# kivez_rl_s.net
KiCad netlist of a schematic drawn in EAGLE
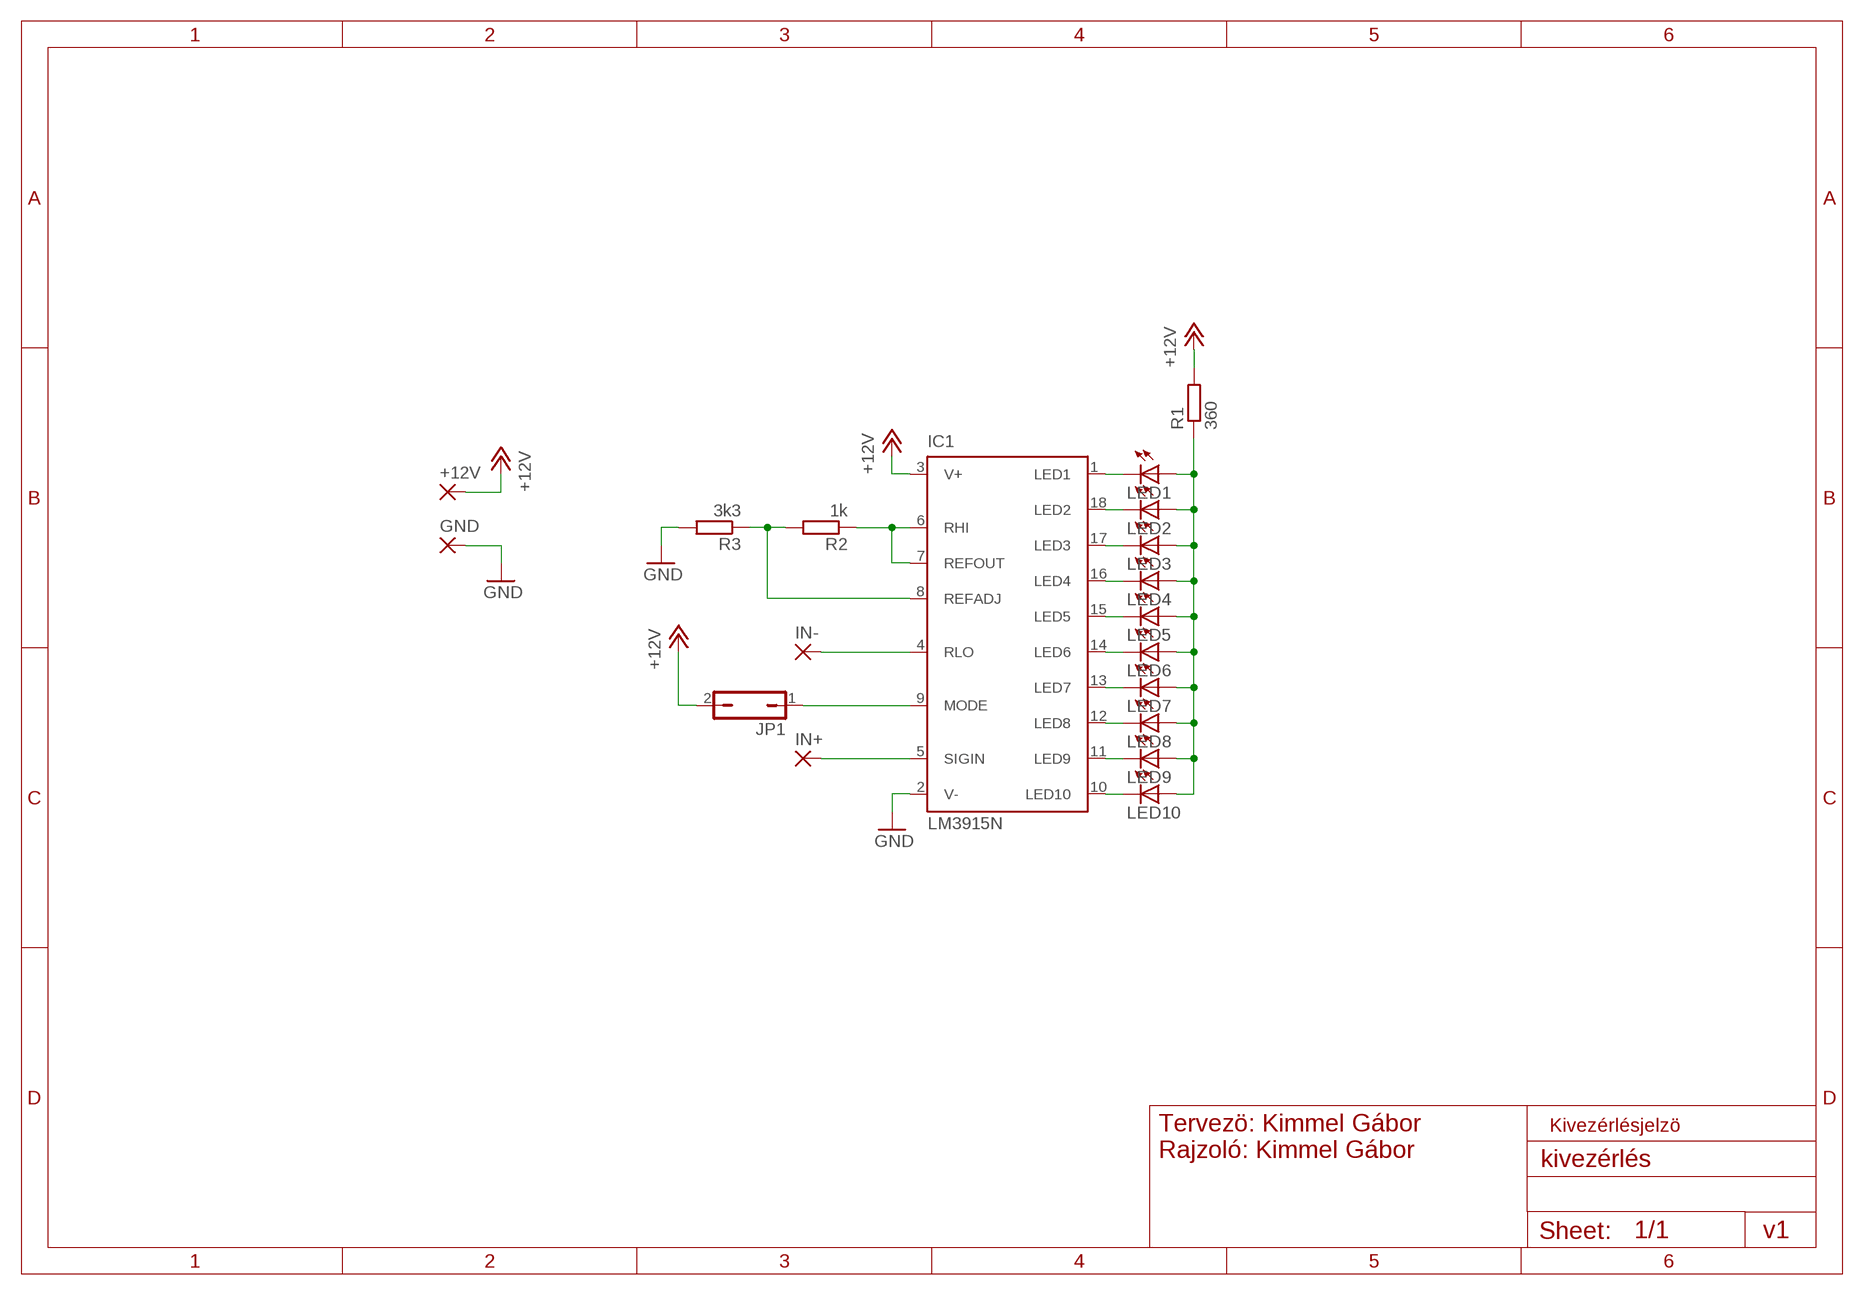
[diagram p0: schematic, sheet 1]

(export (version "E")
  (design (tool "Eeschema 10.0.6"))
  (components
    (comp (ref "+12V")
      (value "2,15/1,0")
      (footprint "eagle-import:2,15_1,0")
      (libsource (lib "eagle-import") (part "2,15/1,0"))
    )
    (comp (ref "GND")
      (value "2,15/1,0")
      (footprint "eagle-import:2,15_1,0")
      (libsource (lib "eagle-import") (part "2,15/1,0"))
    )
    (comp (ref "IC1")
      (value "LM3915N")
      (footprint "eagle-import:DIL18")
      (libsource (lib "eagle-import") (part "LM391N5"))
    )
    (comp (ref "IN+")
      (value "2,15/1,0")
      (footprint "eagle-import:2,15_1,0")
      (libsource (lib "eagle-import") (part "2,15/1,0"))
    )
    (comp (ref "IN-")
      (value "2,15/1,0")
      (footprint "eagle-import:2,15_1,0")
      (libsource (lib "eagle-import") (part "2,15/1,0"))
    )
    (comp (ref "JP1")
      (value "JP1Q")
      (footprint "eagle-import:JP1")
      (libsource (lib "eagle-import") (part "JP1Q"))
    )
    (comp (ref "LED1")
      (value "LED5MM")
      (footprint "eagle-import:LED5MM")
      (libsource (lib "eagle-import") (part "LED5MM"))
    )
    (comp (ref "LED2")
      (value "LED5MM")
      (footprint "eagle-import:LED5MM")
      (libsource (lib "eagle-import") (part "LED5MM"))
    )
    (comp (ref "LED3")
      (value "LED5MM")
      (footprint "eagle-import:LED5MM")
      (libsource (lib "eagle-import") (part "LED5MM"))
    )
    (comp (ref "LED4")
      (value "LED5MM")
      (footprint "eagle-import:LED5MM")
      (libsource (lib "eagle-import") (part "LED5MM"))
    )
    (comp (ref "LED5")
      (value "LED5MM")
      (footprint "eagle-import:LED5MM")
      (libsource (lib "eagle-import") (part "LED5MM"))
    )
    (comp (ref "LED6")
      (value "LED5MM")
      (footprint "eagle-import:LED5MM")
      (libsource (lib "eagle-import") (part "LED5MM"))
    )
    (comp (ref "LED7")
      (value "LED5MM")
      (footprint "eagle-import:LED5MM")
      (libsource (lib "eagle-import") (part "LED5MM"))
    )
    (comp (ref "LED8")
      (value "LED5MM")
      (footprint "eagle-import:LED5MM")
      (libsource (lib "eagle-import") (part "LED5MM"))
    )
    (comp (ref "LED9")
      (value "LED5MM")
      (footprint "eagle-import:LED5MM")
      (libsource (lib "eagle-import") (part "LED5MM"))
    )
    (comp (ref "LED10")
      (value "LED5MM")
      (footprint "eagle-import:LED5MM")
      (libsource (lib "eagle-import") (part "LED5MM"))
    )
    (comp (ref "R1")
      (value "360")
      (footprint "eagle-import:0309_12")
      (libsource (lib "eagle-import") (part "R-EU_0309/12"))
    )
    (comp (ref "R2")
      (value "1k")
      (footprint "eagle-import:0309_12")
      (libsource (lib "eagle-import") (part "R-EU_0309/12"))
    )
    (comp (ref "R3")
      (value "3k3")
      (footprint "eagle-import:0309_12")
      (libsource (lib "eagle-import") (part "R-EU_0309/12"))
    )
  )
  (nets
    (net (code "1") (name "+12V") (class "Default")
      (node (ref "+12V") (pin "1") (pinfunction "P_1") (pintype "passive"))
      (node (ref "IC1") (pin "3") (pinfunction "V+_3") (pintype "power_in"))
      (node (ref "JP1") (pin "2") (pinfunction "2_2") (pintype "passive"))
      (node (ref "R1") (pin "2") (pinfunction "2_2") (pintype "passive"))
    )
    (net (code "2") (name "GND") (class "Default")
      (node (ref "GND") (pin "1") (pinfunction "P_1") (pintype "passive"))
      (node (ref "IC1") (pin "2") (pinfunction "V-_2") (pintype "power_in"))
      (node (ref "R3") (pin "2") (pinfunction "2_2") (pintype "passive"))
    )
    (net (code "3") (name "Net-(IC1-LED1)") (class "Default")
      (node (ref "IC1") (pin "1") (pinfunction "LED1_1") (pintype "output"))
      (node (ref "LED1") (pin "K") (pinfunction "C_K") (pintype "passive"))
    )
    (net (code "4") (name "Net-(IC1-LED2)") (class "Default")
      (node (ref "IC1") (pin "18") (pinfunction "LED2_18") (pintype "output"))
      (node (ref "LED2") (pin "K") (pinfunction "C_K") (pintype "passive"))
    )
    (net (code "5") (name "Net-(IC1-LED3)") (class "Default")
      (node (ref "IC1") (pin "17") (pinfunction "LED3_17") (pintype "output"))
      (node (ref "LED3") (pin "K") (pinfunction "C_K") (pintype "passive"))
    )
    (net (code "6") (name "Net-(IC1-LED4)") (class "Default")
      (node (ref "IC1") (pin "16") (pinfunction "LED4_16") (pintype "output"))
      (node (ref "LED4") (pin "K") (pinfunction "C_K") (pintype "passive"))
    )
    (net (code "7") (name "Net-(IC1-LED5)") (class "Default")
      (node (ref "IC1") (pin "15") (pinfunction "LED5_15") (pintype "output"))
      (node (ref "LED5") (pin "K") (pinfunction "C_K") (pintype "passive"))
    )
    (net (code "8") (name "Net-(IC1-LED6)") (class "Default")
      (node (ref "IC1") (pin "14") (pinfunction "LED6_14") (pintype "output"))
      (node (ref "LED6") (pin "K") (pinfunction "C_K") (pintype "passive"))
    )
    (net (code "9") (name "Net-(IC1-LED7)") (class "Default")
      (node (ref "IC1") (pin "13") (pinfunction "LED7_13") (pintype "output"))
      (node (ref "LED7") (pin "K") (pinfunction "C_K") (pintype "passive"))
    )
    (net (code "10") (name "Net-(IC1-LED8)") (class "Default")
      (node (ref "IC1") (pin "12") (pinfunction "LED8_12") (pintype "output"))
      (node (ref "LED8") (pin "K") (pinfunction "C_K") (pintype "passive"))
    )
    (net (code "11") (name "Net-(IC1-LED9)") (class "Default")
      (node (ref "IC1") (pin "11") (pinfunction "LED9_11") (pintype "output"))
      (node (ref "LED9") (pin "K") (pinfunction "C_K") (pintype "passive"))
    )
    (net (code "12") (name "Net-(IC1-LED10)") (class "Default")
      (node (ref "IC1") (pin "10") (pinfunction "LED10_10") (pintype "output"))
      (node (ref "LED10") (pin "K") (pinfunction "C_K") (pintype "passive"))
    )
    (net (code "13") (name "Net-(IC1-MODE)") (class "Default")
      (node (ref "IC1") (pin "9") (pinfunction "MODE_9") (pintype "input"))
      (node (ref "JP1") (pin "1") (pinfunction "1_1") (pintype "passive"))
    )
    (net (code "14") (name "Net-(IC1-REFADJ)") (class "Default")
      (node (ref "IC1") (pin "8") (pinfunction "REFADJ_8") (pintype "passive"))
      (node (ref "R2") (pin "2") (pinfunction "2_2") (pintype "passive"))
      (node (ref "R3") (pin "1") (pinfunction "1_1") (pintype "passive"))
    )
    (net (code "15") (name "Net-(IC1-REFOUT)") (class "Default")
      (node (ref "IC1") (pin "6") (pinfunction "RHI_6") (pintype "input"))
      (node (ref "IC1") (pin "7") (pinfunction "REFOUT_7") (pintype "output"))
      (node (ref "R2") (pin "1") (pinfunction "1_1") (pintype "passive"))
    )
    (net (code "16") (name "Net-(IC1-RLO)") (class "Default")
      (node (ref "IC1") (pin "4") (pinfunction "RLO_4") (pintype "input"))
      (node (ref "IN-") (pin "1") (pinfunction "P_1") (pintype "passive"))
    )
    (net (code "17") (name "Net-(IC1-SIGIN)") (class "Default")
      (node (ref "IC1") (pin "5") (pinfunction "SIGIN_5") (pintype "input"))
      (node (ref "IN+") (pin "1") (pinfunction "P_1") (pintype "passive"))
    )
    (net (code "18") (name "Net-(LED1-PadA)") (class "Default")
      (node (ref "LED1") (pin "A") (pinfunction "A_A") (pintype "passive"))
      (node (ref "LED10") (pin "A") (pinfunction "A_A") (pintype "passive"))
      (node (ref "LED2") (pin "A") (pinfunction "A_A") (pintype "passive"))
      (node (ref "LED3") (pin "A") (pinfunction "A_A") (pintype "passive"))
      (node (ref "LED4") (pin "A") (pinfunction "A_A") (pintype "passive"))
      (node (ref "LED5") (pin "A") (pinfunction "A_A") (pintype "passive"))
      (node (ref "LED6") (pin "A") (pinfunction "A_A") (pintype "passive"))
      (node (ref "LED7") (pin "A") (pinfunction "A_A") (pintype "passive"))
      (node (ref "LED8") (pin "A") (pinfunction "A_A") (pintype "passive"))
      (node (ref "LED9") (pin "A") (pinfunction "A_A") (pintype "passive"))
      (node (ref "R1") (pin "1") (pinfunction "1_1") (pintype "passive"))
    )
  )
)
